# SCH_EasyEDA-Circuit-Chaser_2025-10-19.net
KiCad netlist of a schematic drawn in EasyEDA
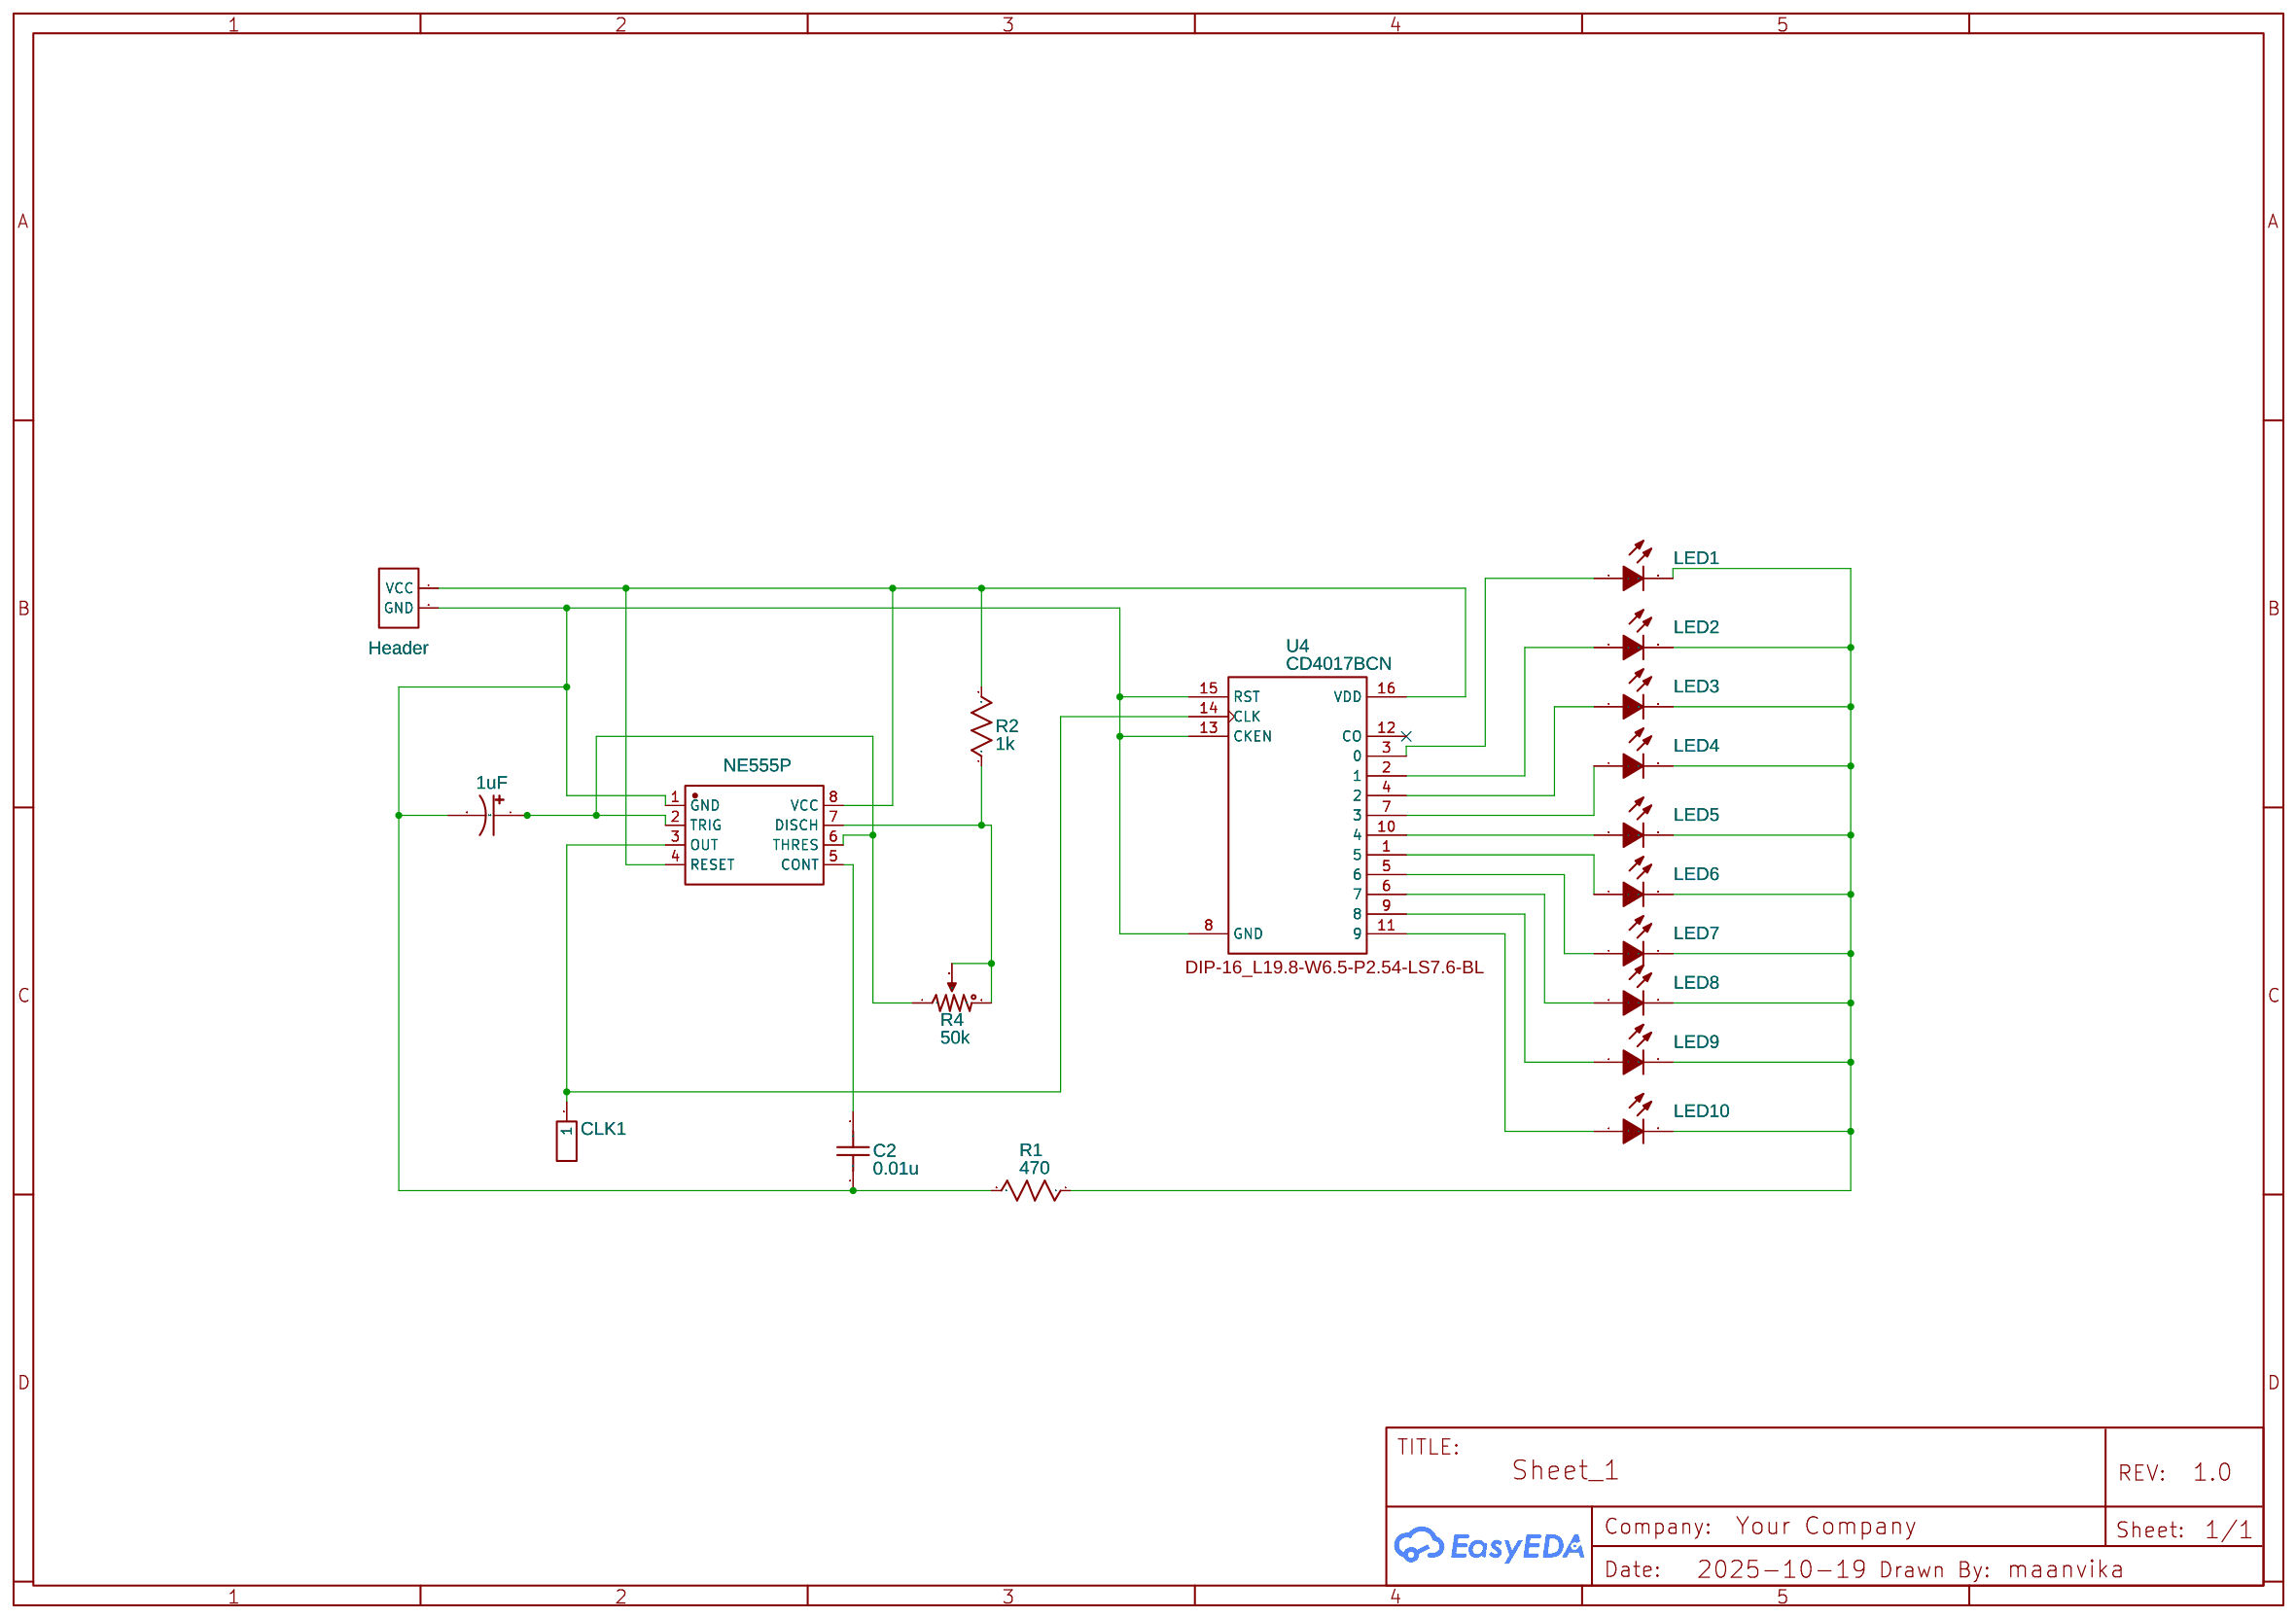
[diagram p0: schematic sheet]

(export (version "E")
  (design (tool "Eeschema 10.0.6"))
  (components
    (comp (ref "C2") (value "0.01u") (libsource (lib "") (part "C_0603_US")))
    (comp (ref "C3")
      (value "1uF")
      (fields (field (name "Manufacturer Part") "UVZ1H010MDD") (field (name "Manufacturer") "Nichicon(尼吉康)"))
      (libsource (lib "") (part "UVZ1H010MDD"))
    )
    (comp (ref "CLK1")
      (value "C81276")
      (fields
        (field (name "Manufacturer Part") "2.54-1*1P针")
        (field (name "Manufacturer") "BOOMELE(Boom Precision Elec)")
      )
      (libsource (lib "") (part "Header-Male-2.54_1x1"))
    )
    (comp (ref "H2") (value "Header") (libsource (lib "") (part "HEADER-FEMALE-2.54_1X2")))
    (comp (ref "LED1") (value "LED_5MM") (libsource (lib "") (part "LED_5MM")))
    (comp (ref "LED2") (value "LED_5MM") (libsource (lib "") (part "LED_5MM")))
    (comp (ref "LED3") (value "LED_5MM") (libsource (lib "") (part "LED_5MM")))
    (comp (ref "LED4") (value "LED_5MM") (libsource (lib "") (part "LED_5MM")))
    (comp (ref "LED5") (value "LED_5MM") (libsource (lib "") (part "LED_5MM")))
    (comp (ref "LED6") (value "LED_5MM") (libsource (lib "") (part "LED_5MM")))
    (comp (ref "LED7") (value "LED_5MM") (libsource (lib "") (part "LED_5MM")))
    (comp (ref "LED8") (value "LED_5MM") (libsource (lib "") (part "LED_5MM")))
    (comp (ref "LED9") (value "LED_5MM") (libsource (lib "") (part "LED_5MM")))
    (comp (ref "LED10") (value "LED_5MM") (libsource (lib "") (part "LED_5MM")))
    (comp (ref "R1")
      (value "470")
      (fields (field (name "Manufacturer Part") "?"))
      (libsource (lib "") (part "Resistor"))
    )
    (comp (ref "R2")
      (value "1k")
      (fields (field (name "Manufacturer Part") "?"))
      (libsource (lib "") (part "Resistor_1"))
    )
    (comp (ref "R4")
      (value "50k")
      (fields (field (name "Manufacturer Part") "?"))
      (libsource (lib "") (part "Potentiometer"))
    )
    (comp (ref "U1")
      (value "NE555P")
      (fields (field (name "Manufacturer") "TI(德州仪器)"))
      (libsource (lib "") (part "NE555P"))
    )
    (comp (ref "U4") (value "CD4017BCN") (libsource (lib "") (part "CD4017BCN")))
  )
  (nets
    (net (code "1") (name "Net-(H2-GND)") (class "Default")
      (node (ref "C2") (pin "1") (pinfunction "1_1") (pintype "unspecified"))
      (node (ref "C3") (pin "2") (pinfunction "2_2") (pintype "unspecified"))
      (node (ref "H2") (pin "2") (pinfunction "GND_2") (pintype "unspecified"))
      (node (ref "R1") (pin "2") (pinfunction "2_2") (pintype "unspecified"))
      (node (ref "U1") (pin "1") (pinfunction "GND_1") (pintype "unspecified"))
      (node (ref "U4") (pin "13") (pinfunction "CKEN_13") (pintype "unspecified"))
      (node (ref "U4") (pin "15") (pinfunction "RST_15") (pintype "unspecified"))
      (node (ref "U4") (pin "8") (pinfunction "GND_8") (pintype "passive"))
    )
    (net (code "2") (name "Net-(H2-VCC)") (class "Default")
      (node (ref "H2") (pin "1") (pinfunction "VCC_1") (pintype "unspecified"))
      (node (ref "R2") (pin "2") (pinfunction "2_2") (pintype "unspecified"))
      (node (ref "U1") (pin "4") (pinfunction "RESET_4") (pintype "unspecified"))
      (node (ref "U1") (pin "8") (pinfunction "VCC_8") (pintype "unspecified"))
      (node (ref "U4") (pin "16") (pinfunction "VDD_16") (pintype "passive"))
    )
    (net (code "3") (name "Net-(LED1-A)") (class "Default")
      (node (ref "LED1") (pin "1") (pinfunction "A_1") (pintype "input"))
      (node (ref "U4") (pin "3") (pinfunction "0_3") (pintype "output"))
    )
    (net (code "4") (name "Net-(LED1-K)") (class "Default")
      (node (ref "LED1") (pin "2") (pinfunction "K_2") (pintype "input"))
      (node (ref "LED10") (pin "2") (pinfunction "K_2") (pintype "input"))
      (node (ref "LED2") (pin "2") (pinfunction "K_2") (pintype "input"))
      (node (ref "LED3") (pin "2") (pinfunction "K_2") (pintype "input"))
      (node (ref "LED4") (pin "2") (pinfunction "K_2") (pintype "input"))
      (node (ref "LED5") (pin "2") (pinfunction "K_2") (pintype "input"))
      (node (ref "LED6") (pin "2") (pinfunction "K_2") (pintype "input"))
      (node (ref "LED7") (pin "2") (pinfunction "K_2") (pintype "input"))
      (node (ref "LED8") (pin "2") (pinfunction "K_2") (pintype "input"))
      (node (ref "LED9") (pin "2") (pinfunction "K_2") (pintype "input"))
      (node (ref "R1") (pin "1") (pinfunction "1_1") (pintype "unspecified"))
    )
    (net (code "5") (name "Net-(LED2-A)") (class "Default")
      (node (ref "LED2") (pin "1") (pinfunction "A_1") (pintype "input"))
      (node (ref "U4") (pin "2") (pinfunction "1_2") (pintype "output"))
    )
    (net (code "6") (name "Net-(LED3-A)") (class "Default")
      (node (ref "LED3") (pin "1") (pinfunction "A_1") (pintype "input"))
      (node (ref "U4") (pin "4") (pinfunction "2_4") (pintype "output"))
    )
    (net (code "7") (name "Net-(LED4-A)") (class "Default")
      (node (ref "LED4") (pin "1") (pinfunction "A_1") (pintype "input"))
      (node (ref "U4") (pin "7") (pinfunction "3_7") (pintype "output"))
    )
    (net (code "8") (name "Net-(LED5-A)") (class "Default")
      (node (ref "LED5") (pin "1") (pinfunction "A_1") (pintype "input"))
      (node (ref "U4") (pin "10") (pinfunction "4_10") (pintype "output"))
    )
    (net (code "9") (name "Net-(LED6-A)") (class "Default")
      (node (ref "LED6") (pin "1") (pinfunction "A_1") (pintype "input"))
      (node (ref "U4") (pin "1") (pinfunction "5_1") (pintype "output"))
    )
    (net (code "10") (name "Net-(LED7-A)") (class "Default")
      (node (ref "LED7") (pin "1") (pinfunction "A_1") (pintype "input"))
      (node (ref "U4") (pin "5") (pinfunction "6_5") (pintype "output"))
    )
    (net (code "11") (name "Net-(LED8-A)") (class "Default")
      (node (ref "LED8") (pin "1") (pinfunction "A_1") (pintype "input"))
      (node (ref "U4") (pin "6") (pinfunction "7_6") (pintype "output"))
    )
    (net (code "12") (name "Net-(LED9-A)") (class "Default")
      (node (ref "LED9") (pin "1") (pinfunction "A_1") (pintype "input"))
      (node (ref "U4") (pin "9") (pinfunction "8_9") (pintype "output"))
    )
    (net (code "13") (name "Net-(LED10-A)") (class "Default")
      (node (ref "LED10") (pin "1") (pinfunction "A_1") (pintype "input"))
      (node (ref "U4") (pin "11") (pinfunction "9_11") (pintype "output"))
    )
    (net (code "14") (name "Net-(R4-2)") (class "Default")
      (node (ref "R2") (pin "1") (pinfunction "1_1") (pintype "unspecified"))
      (node (ref "R4") (pin "2") (pinfunction "3_2") (pintype "unspecified"))
      (node (ref "R4") (pin "3") (pinfunction "2_3") (pintype "unspecified"))
      (node (ref "U1") (pin "7") (pinfunction "DISCH_7") (pintype "unspecified"))
    )
    (net (code "15") (name "Net-(U1-CONT)") (class "Default")
      (node (ref "C2") (pin "2") (pinfunction "2_2") (pintype "unspecified"))
      (node (ref "U1") (pin "5") (pinfunction "CONT_5") (pintype "unspecified"))
    )
    (net (code "16") (name "Net-(U1-OUT)") (class "Default")
      (node (ref "CLK1") (pin "1") (pinfunction "1_1") (pintype "unspecified"))
      (node (ref "U1") (pin "3") (pinfunction "OUT_3") (pintype "unspecified"))
      (node (ref "U4") (pin "14") (pinfunction "CLK_14") (pintype "unspecified"))
    )
    (net (code "17") (name "Net-(U1-THRES)") (class "Default")
      (node (ref "C3") (pin "1") (pinfunction "1_1") (pintype "unspecified"))
      (node (ref "R4") (pin "1") (pinfunction "1_1") (pintype "unspecified"))
      (node (ref "U1") (pin "2") (pinfunction "TRIG_2") (pintype "unspecified"))
      (node (ref "U1") (pin "6") (pinfunction "THRES_6") (pintype "unspecified"))
    )
    (net (code "18") (name "unconnected-(U4-CO-Pad12)") (class "Default")
      (node (ref "U4") (pin "12") (pinfunction "CO_12") (pintype "output+no_connect"))
    )
  )
)
